# ScienceReceiverBoard.net
KiCad netlist of a schematic drawn in Altium Designer
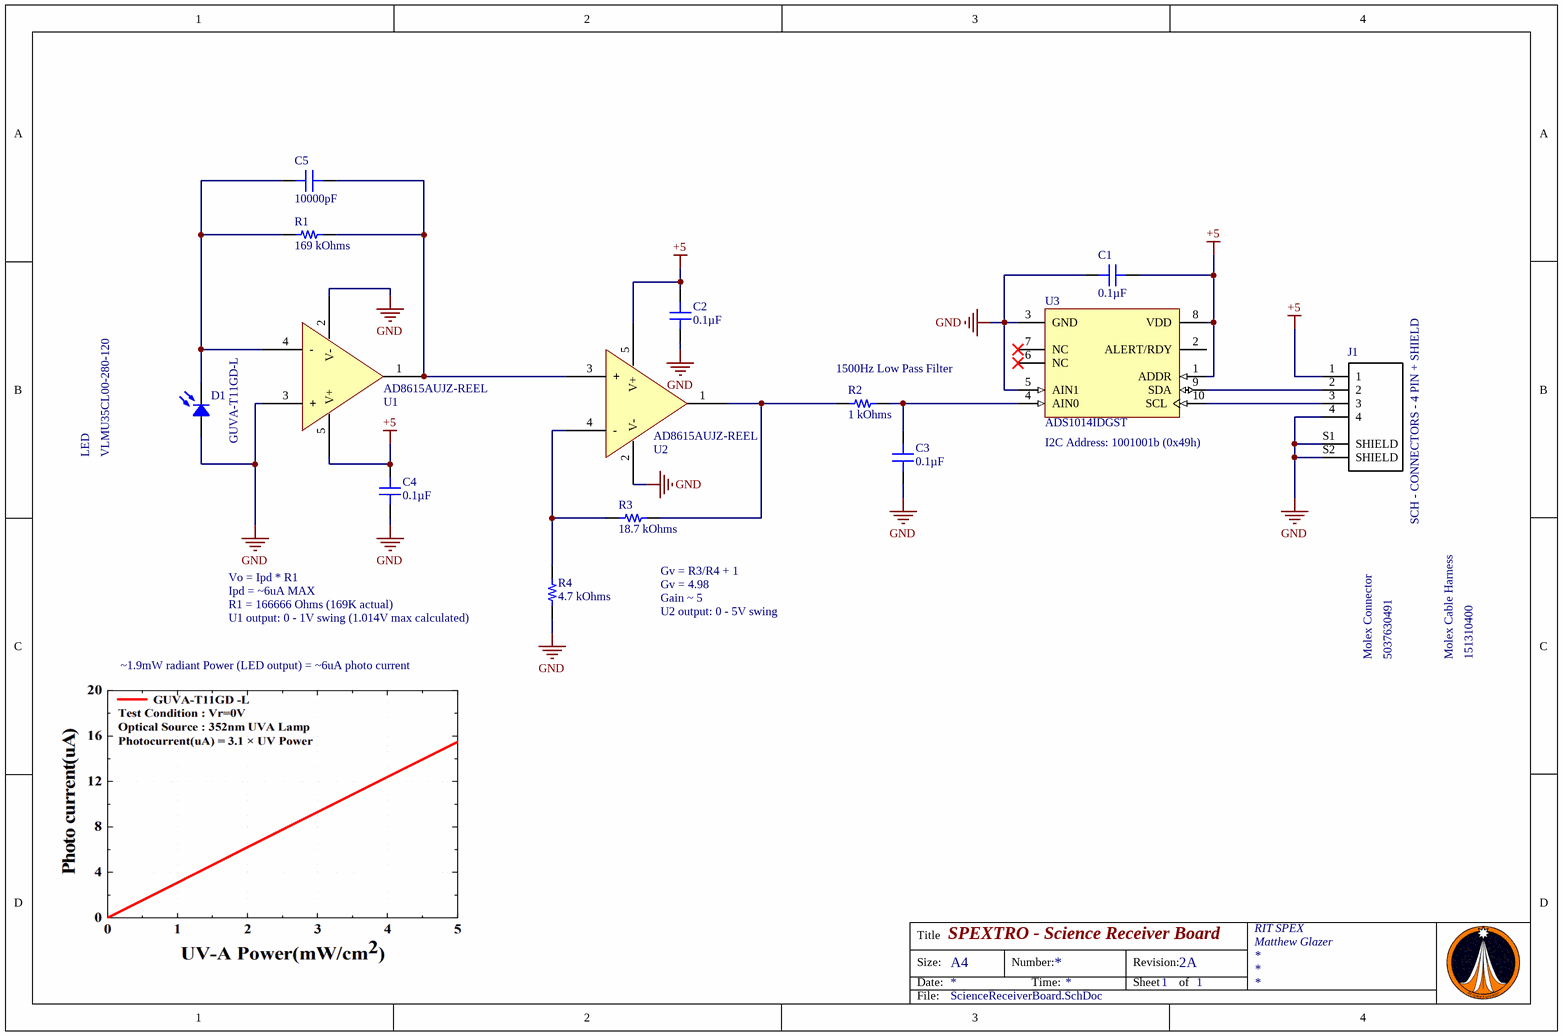
[diagram p0: ScienceReceiverBoard.SchDoc]

(export (version "E")
  (design (tool "Eeschema 10.0.6"))
  (components
    (comp (ref "C1")
      (value "0.1µF")
      (footprint "CAP 0603_1608")
      (description "CAP CER 0.1UF 16V X7R 0603")
      (fields (field (name "PART NUMBER") "CC0603JRX7R7BB104") (field (name "MANUFACTURER") "Yageo"))
      (libsource (lib "Celestial Altium Library - altium_library") (part "Capacitor"))
    )
    (comp (ref "C2")
      (value "0.1µF")
      (footprint "CAP 0603_1608")
      (description "CAP CER 0.1UF 16V X7R 0603")
      (fields (field (name "PART NUMBER") "CC0603JRX7R7BB104") (field (name "MANUFACTURER") "Yageo"))
      (libsource (lib "Celestial Altium Library - altium_library") (part "Capacitor"))
    )
    (comp (ref "C3")
      (value "0.1µF")
      (footprint "CAP 0603_1608")
      (description "CAP CER 0.1UF 16V X7R 0603")
      (fields (field (name "PART NUMBER") "CC0603JRX7R7BB104") (field (name "MANUFACTURER") "Yageo"))
      (libsource (lib "Celestial Altium Library - altium_library") (part "Capacitor"))
    )
    (comp (ref "C4")
      (value "0.1µF")
      (footprint "CAP 0603_1608")
      (description "CAP CER 0.1UF 16V X7R 0603")
      (fields (field (name "PART NUMBER") "CC0603JRX7R7BB104") (field (name "MANUFACTURER") "Yageo"))
      (libsource (lib "Celestial Altium Library - altium_library") (part "Capacitor"))
    )
    (comp (ref "C5")
      (value "10000pF")
      (footprint "CAP 0603_1608")
      (description "CAP CER 10000PF 16V 0603")
      (fields (field (name "PART NUMBER") "EMK107SD103JA-T") (field (name "MANUFACTURER") "Taiyo Yuden"))
      (libsource (lib "Celestial Altium Library - altium_library") (part "Capacitor"))
    )
    (comp (ref "D1")
      (value "GUVA-T11GD-L")
      (footprint "Genicom TO-46-2")
      (description "Photodiode")
      (libsource (lib "ScienceBoardLibrary") (part "PHOTODIODE"))
    )
    (comp (ref "J1")
      (value "SCH - CONNECTORS - 4 PIN + SHIELD")
      (footprint "PCB - CONNECTOR - MOLEX - PICO-LOCK 5037630491")
      (description "Connector Header Surface Mount, Right Angle 4 position 0.039 _1.00mm_")
      (fields (field (name "MF") "Molex") (field (name "MP") "5037630491"))
      (libsource (lib "ScienceBoardLibrary") (part "SCH - CONNECTORS - 4 PIN + SHIELD"))
    )
    (comp (ref "R1")
      (value "169 kOhms")
      (footprint "RES 0603_1608")
      (description "RES 169K OHM 1% 1/10W 0603")
      (fields
        (field (name "PART NUMBER") "RMCF0603FT169K")
        (field (name "MANUFACTURER") "Stackpole Electronics Inc")
      )
      (libsource (lib "Celestial Altium Library - altium_library") (part "Resistor"))
    )
    (comp (ref "R2")
      (value "1 kOhms")
      (footprint "RES 0603_1608")
      (description "RES 1K OHM 1% 1/8W 0603")
      (fields
        (field (name "PART NUMBER") "RNCP0603FTD1K00")
        (field (name "MANUFACTURER") "Stackpole Electronics Inc")
      )
      (libsource (lib "Celestial Altium Library - altium_library") (part "Resistor"))
    )
    (comp (ref "R3")
      (value "18.7 kOhms")
      (footprint "RES 0603_1608")
      (description "RES 18.7K OHM 1% 1/10W 0603")
      (fields
        (field (name "PART NUMBER") "RMCF0603FT18K7")
        (field (name "MANUFACTURER") "Stackpole Electronics Inc")
      )
      (libsource (lib "Celestial Altium Library - altium_library") (part "Resistor"))
    )
    (comp (ref "R4")
      (value "4.7 kOhms")
      (footprint "RES 0603_1608")
      (description "RES 4.7K OHM 1% 1/10W 0603")
      (fields
        (field (name "PART NUMBER") "RMCF0603FT4K70")
        (field (name "MANUFACTURER") "Stackpole Electronics Inc")
      )
      (libsource (lib "Celestial Altium Library - altium_library") (part "Resistor"))
    )
    (comp (ref "U1")
      (value "AD8615AUJZ-REEL")
      (footprint "ANALOG TSOT-23-5 UJ-5")
      (description "IC OPAMP GP 1 CIRCUIT TSOT23-5")
      (fields (field (name "MANUFACTURER") "Analog Devices Inc."))
      (libsource (lib "Celestial Altium Library - altium_library") (part "ANALOG DEV AD8615AUJZ"))
    )
    (comp (ref "U2")
      (value "AD8615AUJZ-REEL")
      (footprint "ANALOG TSOT-23-5 UJ-5")
      (description "IC OPAMP GP 1 CIRCUIT TSOT23-5")
      (fields (field (name "MANUFACTURER") "Analog Devices Inc."))
      (libsource (lib "Celestial Altium Library - altium_library") (part "ANALOG DEV AD8615AUJZ"))
    )
    (comp (ref "U3")
      (value "ADS1014IDGST")
      (footprint "TI-DGS10_L")
      (fields (field (name "MANUFACTURER") "Texas Instruments"))
      (libsource (lib "Altium Content Vault") (part "TI-ADS1014_1114-10"))
    )
  )
  (nets
    (net (code "1") (name "+5") (class "Default")
      (node (ref "C1") (pin "2") (pinfunction "2_2") (pintype "passive"))
      (node (ref "C2") (pin "2") (pinfunction "2_2") (pintype "passive"))
      (node (ref "C4") (pin "2") (pinfunction "2_2") (pintype "passive"))
      (node (ref "J1") (pin "1") (pinfunction "1_1") (pintype "passive"))
      (node (ref "U1") (pin "5") (pinfunction "V+_5") (pintype "passive"))
      (node (ref "U2") (pin "5") (pinfunction "V+_5") (pintype "passive"))
      (node (ref "U3") (pin "1") (pinfunction "ADDR_1") (pintype "input"))
      (node (ref "U3") (pin "8") (pinfunction "VDD_8") (pintype "power_in"))
    )
    (net (code "2") (name "GND") (class "Default")
      (node (ref "C1") (pin "1") (pinfunction "1_1") (pintype "passive"))
      (node (ref "C2") (pin "1") (pinfunction "1_1") (pintype "passive"))
      (node (ref "C3") (pin "1") (pinfunction "1_1") (pintype "passive"))
      (node (ref "C4") (pin "1") (pinfunction "1_1") (pintype "passive"))
      (node (ref "D1") (pin "1") (pinfunction "1_1") (pintype "passive"))
      (node (ref "J1") (pin "4") (pinfunction "4_4") (pintype "passive"))
      (node (ref "J1") (pin "S1") (pinfunction "SHIELD_S1") (pintype "passive"))
      (node (ref "J1") (pin "S2") (pinfunction "SHIELD_S2") (pintype "passive"))
      (node (ref "R4") (pin "1") (pinfunction "1_1") (pintype "passive"))
      (node (ref "U1") (pin "2") (pinfunction "V-_2") (pintype "passive"))
      (node (ref "U1") (pin "3") (pinfunction "+_3") (pintype "passive"))
      (node (ref "U2") (pin "2") (pinfunction "V-_2") (pintype "passive"))
      (node (ref "U3") (pin "3") (pinfunction "GND_3") (pintype "power_in"))
      (node (ref "U3") (pin "5") (pinfunction "AIN1_5") (pintype "input"))
    )
    (net (code "3") (name "Net-(U1--)") (class "Default")
      (node (ref "C5") (pin "1") (pinfunction "1_1") (pintype "passive"))
      (node (ref "D1") (pin "2") (pinfunction "2_2") (pintype "passive"))
      (node (ref "R1") (pin "1") (pinfunction "1_1") (pintype "passive"))
      (node (ref "U1") (pin "4") (pinfunction "-_4") (pintype "passive"))
    )
    (net (code "4") (name "Net-(U1-OUT)") (class "Default")
      (node (ref "C5") (pin "2") (pinfunction "2_2") (pintype "passive"))
      (node (ref "R1") (pin "2") (pinfunction "2_2") (pintype "passive"))
      (node (ref "U1") (pin "1") (pinfunction "OUT_1") (pintype "passive"))
      (node (ref "U2") (pin "3") (pinfunction "+_3") (pintype "passive"))
    )
    (net (code "5") (name "Net-(U2--)") (class "Default")
      (node (ref "R3") (pin "1") (pinfunction "1_1") (pintype "passive"))
      (node (ref "R4") (pin "2") (pinfunction "2_2") (pintype "passive"))
      (node (ref "U2") (pin "4") (pinfunction "-_4") (pintype "passive"))
    )
    (net (code "6") (name "Net-(U2-OUT)") (class "Default")
      (node (ref "R2") (pin "1") (pinfunction "1_1") (pintype "passive"))
      (node (ref "R3") (pin "2") (pinfunction "2_2") (pintype "passive"))
      (node (ref "U2") (pin "1") (pinfunction "OUT_1") (pintype "passive"))
    )
    (net (code "7") (name "Net-(U3-AIN0)") (class "Default")
      (node (ref "C3") (pin "2") (pinfunction "2_2") (pintype "passive"))
      (node (ref "R2") (pin "2") (pinfunction "2_2") (pintype "passive"))
      (node (ref "U3") (pin "4") (pinfunction "AIN0_4") (pintype "input"))
    )
    (net (code "8") (name "Net-(U3-SCL)") (class "Default")
      (node (ref "J1") (pin "3") (pinfunction "3_3") (pintype "passive"))
      (node (ref "U3") (pin "10") (pinfunction "SCL_10") (pintype "input"))
    )
    (net (code "9") (name "Net-(U3-SDA)") (class "Default")
      (node (ref "J1") (pin "2") (pinfunction "2_2") (pintype "passive"))
      (node (ref "U3") (pin "9") (pinfunction "SDA_9") (pintype "bidirectional"))
    )
    (net (code "10") (name "unconnected-(U3-ALERT{slash}RDY-Pad2)") (class "Default")
      (node (ref "U3") (pin "2") (pinfunction "ALERT/RDY_2") (pintype "open_collector"))
    )
    (net (code "11") (name "unconnected-(U3-NC-Pad6)") (class "Default")
      (node (ref "U3") (pin "6") (pinfunction "NC_6") (pintype "passive+no_connect"))
    )
    (net (code "12") (name "unconnected-(U3-NC-Pad7)") (class "Default")
      (node (ref "U3") (pin "7") (pinfunction "NC_7") (pintype "passive+no_connect"))
    )
  )
)
